# Sheet2_-.net
KiCad netlist of a schematic drawn in Altium Designer
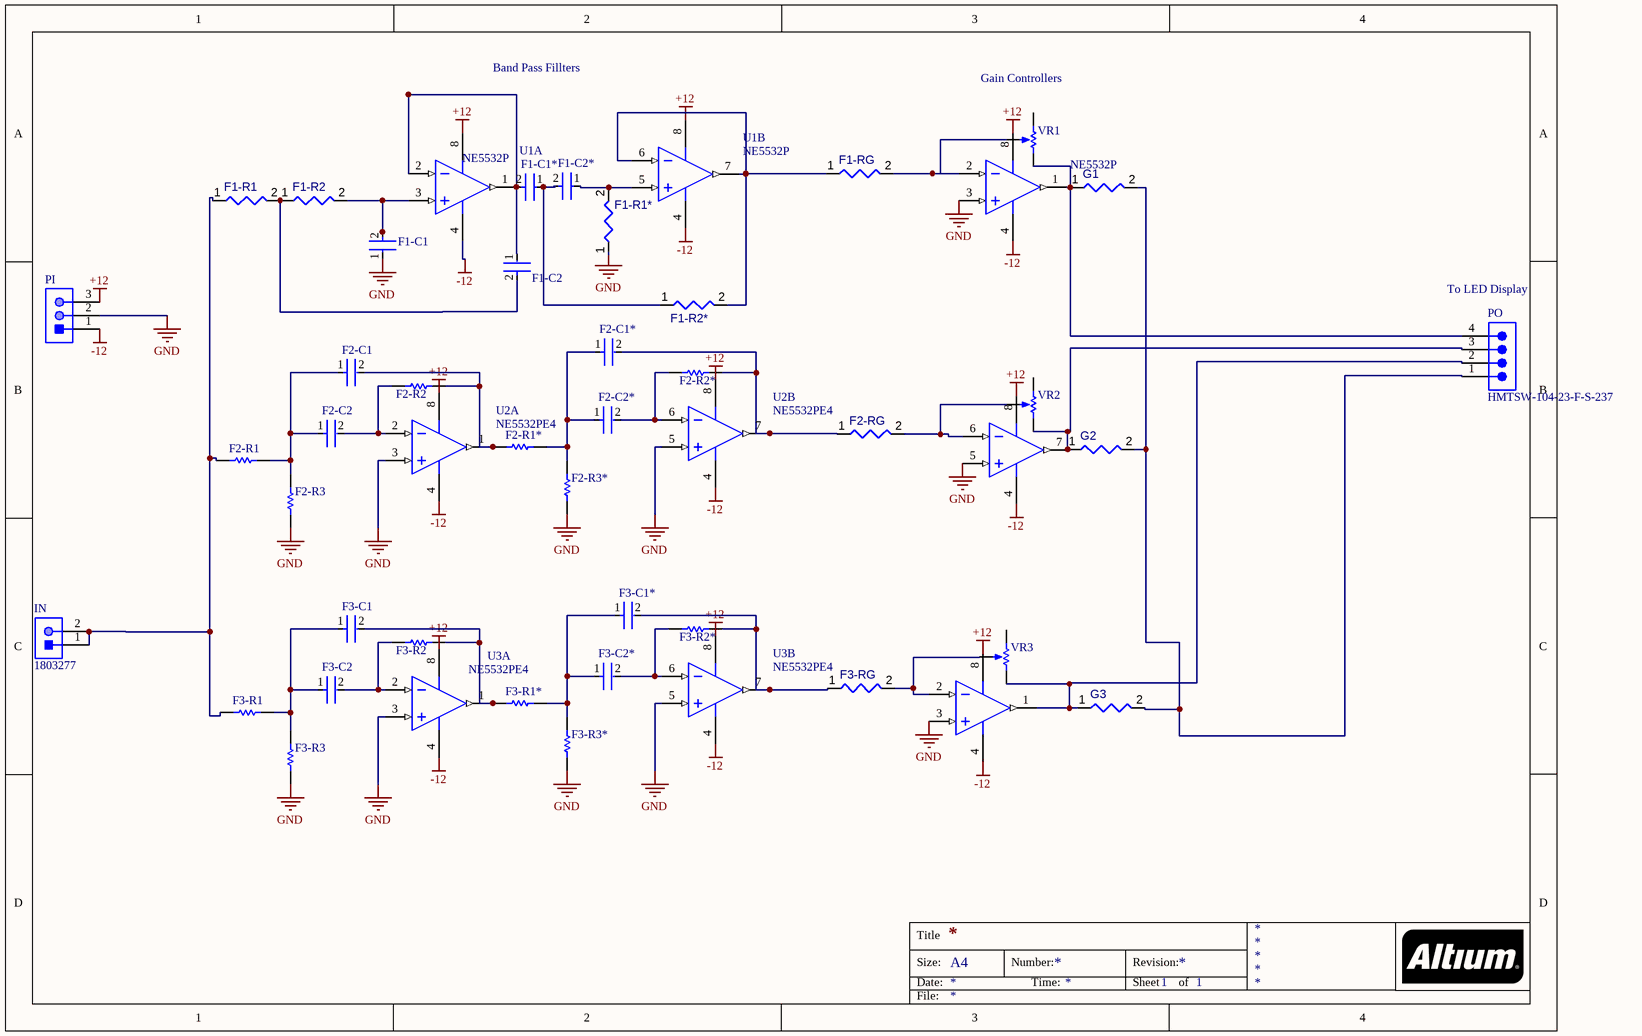
[diagram p0: Sheet2 -.SchDoc]

(export (version "E")
  (design (tool "Eeschema 10.0.6"))
  (components
    (comp (ref "F1-C1")
      (value "VY1102M35Y5UQ6TV0")
      (footprint "FP-VY1102M35Y5UQ6TV0-MFG")
      (description "CAP CER 1000PF 760VAC Y5U RADIAL")
      (fields (field (name "VOLTAGE") "500V") (field (name "TOLERANCE") "20%"))
      (libsource (lib "Altium Content Vault") (part "6d4d395cd7362dd47ce0157d173177e"))
    )
    (comp (ref "F1-C1*")
      (value "VY1102M35Y5UQ6TV0")
      (footprint "FP-VY1102M35Y5UQ6TV0-MFG")
      (description "CAP CER 1000PF 760VAC Y5U RADIAL")
      (fields (field (name "VOLTAGE") "500V") (field (name "TOLERANCE") "20%"))
      (libsource (lib "Altium Content Vault") (part "6d4d395cd7362dd47ce0157d173177e"))
    )
    (comp (ref "F1-C2")
      (value "VY1102M35Y5UQ6TV0")
      (footprint "FP-VY1102M35Y5UQ6TV0-MFG")
      (description "CAP CER 1000PF 760VAC Y5U RADIAL")
      (fields (field (name "VOLTAGE") "500V") (field (name "TOLERANCE") "20%"))
      (libsource (lib "Altium Content Vault") (part "6d4d395cd7362dd47ce0157d173177e"))
    )
    (comp (ref "F1-C2*")
      (value "VY1102M35Y5UQ6TV0")
      (footprint "FP-VY1102M35Y5UQ6TV0-MFG")
      (description "CAP CER 1000PF 760VAC Y5U RADIAL")
      (fields (field (name "VOLTAGE") "500V") (field (name "TOLERANCE") "20%"))
      (libsource (lib "Altium Content Vault") (part "6d4d395cd7362dd47ce0157d173177e"))
    )
    (comp (ref "F1-R1")
      (value "MFR-25FBF52-2K21")
      (footprint "RESA60-630X240")
      (description "Axial Resistor, 2.21 KOhm, +/- 1%, 0.25 W, -55 to 155 degC, 2-Pin THD, RoHS, Bulk")
      (fields (field (name "TOLERANCE") "1%") (field (name "POWER") "250mW"))
      (libsource (lib "Senuda Ratnayake") (part "RES-2"))
    )
    (comp (ref "F1-R1*")
      (value "MFR-25FBF52-2K21")
      (footprint "RESA60-630X240")
      (description "Axial Resistor, 2.21 KOhm, +/- 1%, 0.25 W, -55 to 155 degC, 2-Pin THD, RoHS, Bulk")
      (fields (field (name "TOLERANCE") "1%") (field (name "POWER") "250mW"))
      (libsource (lib "Senuda Ratnayake") (part "RES-2"))
    )
    (comp (ref "F1-R2")
      (value "MFR-25FBF52-2K21")
      (footprint "RESA60-630X240")
      (description "Axial Resistor, 2.21 KOhm, +/- 1%, 0.25 W, -55 to 155 degC, 2-Pin THD, RoHS, Bulk")
      (fields (field (name "TOLERANCE") "1%") (field (name "POWER") "250mW"))
      (libsource (lib "Senuda Ratnayake") (part "RES-2"))
    )
    (comp (ref "F1-R2*")
      (value "MFR-25FBF52-2K21")
      (footprint "RESA60-630X240")
      (description "Axial Resistor, 2.21 KOhm, +/- 1%, 0.25 W, -55 to 155 degC, 2-Pin THD, RoHS, Bulk")
      (fields (field (name "TOLERANCE") "1%") (field (name "POWER") "250mW"))
      (libsource (lib "Senuda Ratnayake") (part "RES-2"))
    )
    (comp (ref "F1-RG")
      (value "MFR-25FBF52-2K21")
      (footprint "RESA60-630X240")
      (description "Axial Resistor, 2.21 KOhm, +/- 1%, 0.25 W, -55 to 155 degC, 2-Pin THD, RoHS, Bulk")
      (fields (field (name "TOLERANCE") "1%") (field (name "POWER") "250mW"))
      (libsource (lib "Senuda Ratnayake") (part "RES-2"))
    )
    (comp (ref "F2-C1")
      (value "VY2102M29Y5US6TV7")
      (footprint "FP-VY2102M29Y5US6TV7-MFG")
      (fields (field (name "VOLTAGE") "300V") (field (name "TOLERANCE") "20%"))
      (libsource (lib "Altium Content Vault") (part "11868f565c42a9108669ba33697ecf6"))
    )
    (comp (ref "F2-C1*")
      (value "VY2102M29Y5US6TV7")
      (footprint "FP-VY2102M29Y5US6TV7-MFG")
      (fields (field (name "VOLTAGE") "300V") (field (name "TOLERANCE") "20%"))
      (libsource (lib "Altium Content Vault") (part "11868f565c42a9108669ba33697ecf6"))
    )
    (comp (ref "F2-C2")
      (value "VY2102M29Y5US6TV7")
      (footprint "FP-VY2102M29Y5US6TV7-MFG")
      (fields (field (name "VOLTAGE") "300V") (field (name "TOLERANCE") "20%"))
      (libsource (lib "Altium Content Vault") (part "11868f565c42a9108669ba33697ecf6"))
    )
    (comp (ref "F2-C2*")
      (value "VY2102M29Y5US6TV7")
      (footprint "FP-VY2102M29Y5US6TV7-MFG")
      (fields (field (name "VOLTAGE") "300V") (field (name "TOLERANCE") "20%"))
      (libsource (lib "Altium Content Vault") (part "11868f565c42a9108669ba33697ecf6"))
    )
    (comp (ref "F2-R1")
      (value "MFR-25FBF52-2K21")
      (footprint "RESA60-630X240")
      (description "Axial Resistor, 2.21 KOhm, +/- 1%, 0.25 W, -55 to 155 degC, 2-Pin THD, RoHS, Bulk")
      (libsource (lib "Altium Content Vault") (part "RES-2"))
    )
    (comp (ref "F2-R1*")
      (value "MFR-25FBF52-2K21")
      (footprint "RESA60-630X240")
      (description "Axial Resistor, 2.21 KOhm, +/- 1%, 0.25 W, -55 to 155 degC, 2-Pin THD, RoHS, Bulk")
      (libsource (lib "Altium Content Vault") (part "RES-2"))
    )
    (comp (ref "F2-R2")
      (value "MFR-25FBF5210K")
      (footprint "RESA60-630X240")
      (description "Axial Resistor, 10 KOhm, +/- 1%, 0.25 W, -55 to 155 degC, 2-Pin THD, RoHS, Bulk")
      (fields (field (name "TOLERANCE") "1%") (field (name "MANUFACTURER") "Yageo"))
      (libsource (lib "Altium Content Vault") (part "RES-2"))
    )
    (comp (ref "F2-R2*")
      (value "MFR-25FBF5210K")
      (footprint "RESA60-630X240")
      (description "Axial Resistor, 10 KOhm, +/- 1%, 0.25 W, -55 to 155 degC, 2-Pin THD, RoHS, Bulk")
      (fields (field (name "TOLERANCE") "1%") (field (name "MANUFACTURER") "Yageo"))
      (libsource (lib "Altium Content Vault") (part "RES-2"))
    )
    (comp (ref "F2-R3")
      (value "MFR-25FBF5210K")
      (footprint "RESA60-630X240")
      (description "Axial Resistor, 10 KOhm, +/- 1%, 0.25 W, -55 to 155 degC, 2-Pin THD, RoHS, Bulk")
      (fields (field (name "TOLERANCE") "1%") (field (name "MANUFACTURER") "Yageo"))
      (libsource (lib "Altium Content Vault") (part "RES-2"))
    )
    (comp (ref "F2-R3*")
      (value "MFR-25FBF5210K")
      (footprint "RESA60-630X240")
      (description "Axial Resistor, 10 KOhm, +/- 1%, 0.25 W, -55 to 155 degC, 2-Pin THD, RoHS, Bulk")
      (fields (field (name "TOLERANCE") "1%") (field (name "MANUFACTURER") "Yageo"))
      (libsource (lib "Altium Content Vault") (part "RES-2"))
    )
    (comp (ref "F2-RG")
      (value "MFR-25FBF52-2K21")
      (footprint "RESA60-630X240")
      (description "Axial Resistor, 2.21 KOhm, +/- 1%, 0.25 W, -55 to 155 degC, 2-Pin THD, RoHS, Bulk")
      (fields (field (name "TOLERANCE") "1%") (field (name "POWER") "250mW"))
      (libsource (lib "Senuda Ratnayake") (part "RES-2"))
    )
    (comp (ref "F3-C1")
      (value "VY2102M29Y5US6TV7")
      (footprint "FP-VY2102M29Y5US6TV7-MFG")
      (fields (field (name "VOLTAGE") "300V") (field (name "TOLERANCE") "20%"))
      (libsource (lib "Altium Content Vault") (part "11868f565c42a9108669ba33697ecf6"))
    )
    (comp (ref "F3-C1*")
      (value "VY2102M29Y5US6TV7")
      (footprint "FP-VY2102M29Y5US6TV7-MFG")
      (fields (field (name "VOLTAGE") "300V") (field (name "TOLERANCE") "20%"))
      (libsource (lib "Altium Content Vault") (part "11868f565c42a9108669ba33697ecf6"))
    )
    (comp (ref "F3-C2")
      (value "VY2102M29Y5US6TV7")
      (footprint "FP-VY2102M29Y5US6TV7-MFG")
      (fields (field (name "VOLTAGE") "300V") (field (name "TOLERANCE") "20%"))
      (libsource (lib "Altium Content Vault") (part "11868f565c42a9108669ba33697ecf6"))
    )
    (comp (ref "F3-C2*")
      (value "VY2102M29Y5US6TV7")
      (footprint "FP-VY2102M29Y5US6TV7-MFG")
      (fields (field (name "VOLTAGE") "300V") (field (name "TOLERANCE") "20%"))
      (libsource (lib "Altium Content Vault") (part "11868f565c42a9108669ba33697ecf6"))
    )
    (comp (ref "F3-R1")
      (value "MFR-25FBF52-2K21")
      (footprint "RESA60-630X240")
      (description "Axial Resistor, 2.21 KOhm, +/- 1%, 0.25 W, -55 to 155 degC, 2-Pin THD, RoHS, Bulk")
      (libsource (lib "Altium Content Vault") (part "RES-2"))
    )
    (comp (ref "F3-R1*")
      (value "MFR-25FBF52-2K21")
      (footprint "RESA60-630X240")
      (description "Axial Resistor, 2.21 KOhm, +/- 1%, 0.25 W, -55 to 155 degC, 2-Pin THD, RoHS, Bulk")
      (libsource (lib "Altium Content Vault") (part "RES-2"))
    )
    (comp (ref "F3-R2")
      (value "MFR-25FBF5210K")
      (footprint "RESA60-630X240")
      (description "Axial Resistor, 10 KOhm, +/- 1%, 0.25 W, -55 to 155 degC, 2-Pin THD, RoHS, Bulk")
      (fields (field (name "TOLERANCE") "1%") (field (name "MANUFACTURER") "Yageo"))
      (libsource (lib "Altium Content Vault") (part "RES-2"))
    )
    (comp (ref "F3-R2*")
      (value "MFR-25FBF5210K")
      (footprint "RESA60-630X240")
      (description "Axial Resistor, 10 KOhm, +/- 1%, 0.25 W, -55 to 155 degC, 2-Pin THD, RoHS, Bulk")
      (fields (field (name "TOLERANCE") "1%") (field (name "MANUFACTURER") "Yageo"))
      (libsource (lib "Altium Content Vault") (part "RES-2"))
    )
    (comp (ref "F3-R3")
      (value "MFR-25FBF5210K")
      (footprint "RESA60-630X240")
      (description "Axial Resistor, 10 KOhm, +/- 1%, 0.25 W, -55 to 155 degC, 2-Pin THD, RoHS, Bulk")
      (fields (field (name "TOLERANCE") "1%") (field (name "MANUFACTURER") "Yageo"))
      (libsource (lib "Altium Content Vault") (part "RES-2"))
    )
    (comp (ref "F3-R3*")
      (value "MFR-25FBF5210K")
      (footprint "RESA60-630X240")
      (description "Axial Resistor, 10 KOhm, +/- 1%, 0.25 W, -55 to 155 degC, 2-Pin THD, RoHS, Bulk")
      (fields (field (name "TOLERANCE") "1%") (field (name "MANUFACTURER") "Yageo"))
      (libsource (lib "Altium Content Vault") (part "RES-2"))
    )
    (comp (ref "F3-RG")
      (value "MFR-25FBF52-2K21")
      (footprint "RESA60-630X240")
      (description "Axial Resistor, 2.21 KOhm, +/- 1%, 0.25 W, -55 to 155 degC, 2-Pin THD, RoHS, Bulk")
      (fields (field (name "TOLERANCE") "1%") (field (name "POWER") "250mW"))
      (libsource (lib "Senuda Ratnayake") (part "RES-2"))
    )
    (comp (ref "G1")
      (value "MFR-25FBF52-2K21")
      (footprint "RESA60-630X240")
      (description "Axial Resistor, 2.21 KOhm, +/- 1%, 0.25 W, -55 to 155 degC, 2-Pin THD, RoHS, Bulk")
      (fields (field (name "TOLERANCE") "1%") (field (name "POWER") "250mW"))
      (libsource (lib "Senuda Ratnayake") (part "RES-2"))
    )
    (comp (ref "G2")
      (value "MFR-25FBF52-2K21")
      (footprint "RESA60-630X240")
      (description "Axial Resistor, 2.21 KOhm, +/- 1%, 0.25 W, -55 to 155 degC, 2-Pin THD, RoHS, Bulk")
      (fields (field (name "TOLERANCE") "1%") (field (name "POWER") "250mW"))
      (libsource (lib "Senuda Ratnayake") (part "RES-2"))
    )
    (comp (ref "G3")
      (value "MFR-25FBF52-2K21")
      (footprint "RESA60-630X240")
      (description "Axial Resistor, 2.21 KOhm, +/- 1%, 0.25 W, -55 to 155 degC, 2-Pin THD, RoHS, Bulk")
      (fields (field (name "TOLERANCE") "1%") (field (name "POWER") "250mW"))
      (libsource (lib "Senuda Ratnayake") (part "RES-2"))
    )
    (comp (ref "IN")
      (value "1803277")
      (footprint "PHOE-1803277_V")
      (description "Male Header, Pitch 3.81 mm, 1 x 2 Position, Height 7.25 mm, Tail Length 3.4 mm, RoHS, Bulk")
      (fields (field (name "MANUFACTURER") "Phoenix Contact"))
      (libsource (lib "Senuda Ratnayake") (part "CN-1P-M-R2"))
    )
    (comp (ref "PI")
      (value "B3P-VH(LF)(SN)")
      (footprint "JST-B3P-VH(LF)(SN)-3_V")
      (fields (field (name "MANUFACTURER") "JST"))
      (libsource (lib "Senuda Ratnayake") (part "CN-1P-M-R3"))
    )
    (comp (ref "PO")
      (value "HMTSW-104-23-F-S-237")
      (footprint "SMTC-HMTSW-104-23-X-S-237")
      (fields (field (name "MANUFACTURER") "Samtec"))
      (libsource (lib "Altium Content Vault") (part "SMTC-HMTSW-104-23-X-S-237"))
    )
    (comp (ref "U1")
      (value "NE5532P")
      (footprint "P0008A")
      (fields (field (name "MANUFACTURER") "Texas Instruments"))
      (libsource (lib "Altium Content Vault") (part "TI-AMP-D6-2-8_D"))
    )
    (comp (ref "U2")
      (value "NE5532PE4")
      (footprint "TI-P8")
      (fields (field (name "MANUFACTURER") "Texas Instruments"))
      (libsource (lib "Altium Content Vault") (part "TI-AMP-D6-2-8_D"))
    )
    (comp (ref "U3")
      (value "NE5532PE4")
      (footprint "TI-P8")
      (fields (field (name "MANUFACTURER") "Texas Instruments"))
      (libsource (lib "Altium Content Vault") (part "TI-AMP-D6-2-8_D"))
    )
    (comp (ref "U4")
      (value "NE5532P")
      (footprint "P0008A")
      (fields (field (name "MANUFACTURER") "Texas Instruments"))
      (libsource (lib "Altium Content Vault") (part "TI-AMP-D6-2-8_D"))
    )
    (comp (ref "U5")
      (value "NE5532P")
      (footprint "P0008A")
      (fields (field (name "MANUFACTURER") "Texas Instruments"))
      (libsource (lib "Altium Content Vault") (part "TI-AMP-D6-2-8_D"))
    )
    (comp (ref "VR1")
      (value "3852A-282-103AL")
      (footprint "BOUR-3852A-282-103AL-3_V")
      (description "Diameter Panel Control, 10 KOhm, +/- 10%, 2 W, -1 to 125 degC, 3-Pin THD, RoHS, Bulk")
      (fields (field (name "TOLERANCE") "±10%") (field (name "MANUFACTURER") "Bourns"))
      (libsource (lib "Altium Content Vault") (part "RES-POT-3"))
    )
    (comp (ref "VR2")
      (value "3852A-282-103AL")
      (footprint "BOUR-3852A-282-103AL-3_V")
      (description "Diameter Panel Control, 10 KOhm, +/- 10%, 2 W, -1 to 125 degC, 3-Pin THD, RoHS, Bulk")
      (fields (field (name "TOLERANCE") "±10%") (field (name "MANUFACTURER") "Bourns"))
      (libsource (lib "Altium Content Vault") (part "RES-POT-3"))
    )
    (comp (ref "VR3")
      (value "3852A-282-103AL")
      (footprint "BOUR-3852A-282-103AL-3_V")
      (description "Diameter Panel Control, 10 KOhm, +/- 10%, 2 W, -1 to 125 degC, 3-Pin THD, RoHS, Bulk")
      (fields (field (name "TOLERANCE") "±10%") (field (name "MANUFACTURER") "Bourns"))
      (libsource (lib "Altium Content Vault") (part "RES-POT-3"))
    )
  )
  (nets
    (net (code "1") (name "+12") (class "Default")
      (node (ref "PI") (pin "3") (pinfunction "3_3") (pintype "passive"))
      (node (ref "U1") (pin "8") (pinfunction "VCC+_8") (pintype "power_in"))
      (node (ref "U2") (pin "8") (pinfunction "VCC+_8") (pintype "power_in"))
      (node (ref "U3") (pin "8") (pinfunction "VCC+_8") (pintype "power_in"))
      (node (ref "U4") (pin "8") (pinfunction "VCC+_8") (pintype "power_in"))
      (node (ref "U5") (pin "8") (pinfunction "VCC+_8") (pintype "power_in"))
    )
    (net (code "2") (name "-12") (class "Default")
      (node (ref "PI") (pin "1") (pinfunction "1_1") (pintype "passive"))
      (node (ref "U1") (pin "4") (pinfunction "VCC-_4") (pintype "power_in"))
      (node (ref "U2") (pin "4") (pinfunction "VCC-_4") (pintype "power_in"))
      (node (ref "U3") (pin "4") (pinfunction "VCC-_4") (pintype "power_in"))
      (node (ref "U4") (pin "4") (pinfunction "VCC-_4") (pintype "power_in"))
      (node (ref "U5") (pin "4") (pinfunction "VCC-_4") (pintype "power_in"))
    )
    (net (code "3") (name "GND") (class "Default")
      (node (ref "F1-C1") (pin "1") (pinfunction "1_1") (pintype "passive"))
      (node (ref "F1-R1*") (pin "1") (pinfunction "1_1") (pintype "passive"))
      (node (ref "F2-R3") (pin "1") (pinfunction "1_1") (pintype "passive"))
      (node (ref "F2-R3*") (pin "1") (pinfunction "1_1") (pintype "passive"))
      (node (ref "F3-R3") (pin "1") (pinfunction "1_1") (pintype "passive"))
      (node (ref "F3-R3*") (pin "1") (pinfunction "1_1") (pintype "passive"))
      (node (ref "PI") (pin "2") (pinfunction "2_2") (pintype "passive"))
      (node (ref "U2") (pin "3") (pinfunction "IN1+_3") (pintype "input"))
      (node (ref "U2") (pin "5") (pinfunction "IN2+_5") (pintype "input"))
      (node (ref "U3") (pin "3") (pinfunction "IN1+_3") (pintype "input"))
      (node (ref "U3") (pin "5") (pinfunction "IN2+_5") (pintype "input"))
      (node (ref "U4") (pin "3") (pinfunction "IN1+_3") (pintype "input"))
      (node (ref "U4") (pin "5") (pinfunction "IN2+_5") (pintype "input"))
      (node (ref "U5") (pin "3") (pinfunction "IN1+_3") (pintype "input"))
    )
    (net (code "4") (name "Net-(F1-C1*-Pad1)") (class "Default")
      (node (ref "F1-C1*") (pin "1") (pinfunction "1_1") (pintype "passive"))
      (node (ref "F1-C2*") (pin "2") (pinfunction "2_2") (pintype "passive"))
      (node (ref "F1-R2*") (pin "1") (pinfunction "1_1") (pintype "passive"))
    )
    (net (code "5") (name "Net-(F1-C2-Pad2)") (class "Default")
      (node (ref "F1-C2") (pin "2") (pinfunction "2_2") (pintype "passive"))
      (node (ref "F1-R1") (pin "2") (pinfunction "2_2") (pintype "passive"))
      (node (ref "F1-R2") (pin "1") (pinfunction "1_1") (pintype "passive"))
    )
    (net (code "6") (name "Net-(F1-R1-Pad1)") (class "Default")
      (node (ref "F1-R1") (pin "1") (pinfunction "1_1") (pintype "passive"))
      (node (ref "F2-R1") (pin "1") (pinfunction "1_1") (pintype "passive"))
      (node (ref "F3-R1") (pin "1") (pinfunction "1_1") (pintype "passive"))
      (node (ref "IN") (pin "1") (pinfunction "1_1") (pintype "passive"))
      (node (ref "IN") (pin "2") (pinfunction "2_2") (pintype "passive"))
    )
    (net (code "7") (name "Net-(F2-C1*-Pad1)") (class "Default")
      (node (ref "F2-C1*") (pin "1") (pinfunction "1_1") (pintype "passive"))
      (node (ref "F2-C2*") (pin "1") (pinfunction "1_1") (pintype "passive"))
      (node (ref "F2-R1*") (pin "2") (pinfunction "2_2") (pintype "passive"))
      (node (ref "F2-R3*") (pin "2") (pinfunction "2_2") (pintype "passive"))
    )
    (net (code "8") (name "Net-(F2-C1-Pad1)") (class "Default")
      (node (ref "F2-C1") (pin "1") (pinfunction "1_1") (pintype "passive"))
      (node (ref "F2-C2") (pin "1") (pinfunction "1_1") (pintype "passive"))
      (node (ref "F2-R1") (pin "2") (pinfunction "2_2") (pintype "passive"))
      (node (ref "F2-R3") (pin "2") (pinfunction "2_2") (pintype "passive"))
    )
    (net (code "9") (name "Net-(F3-C1*-Pad1)") (class "Default")
      (node (ref "F3-C1*") (pin "1") (pinfunction "1_1") (pintype "passive"))
      (node (ref "F3-C2*") (pin "1") (pinfunction "1_1") (pintype "passive"))
      (node (ref "F3-R1*") (pin "2") (pinfunction "2_2") (pintype "passive"))
      (node (ref "F3-R3*") (pin "2") (pinfunction "2_2") (pintype "passive"))
    )
    (net (code "10") (name "Net-(F3-C1-Pad1)") (class "Default")
      (node (ref "F3-C1") (pin "1") (pinfunction "1_1") (pintype "passive"))
      (node (ref "F3-C2") (pin "1") (pinfunction "1_1") (pintype "passive"))
      (node (ref "F3-R1") (pin "2") (pinfunction "2_2") (pintype "passive"))
      (node (ref "F3-R3") (pin "2") (pinfunction "2_2") (pintype "passive"))
    )
    (net (code "11") (name "Net-(G1-Pad2)") (class "Default")
      (node (ref "G1") (pin "2") (pinfunction "2_2") (pintype "passive"))
      (node (ref "G2") (pin "2") (pinfunction "2_2") (pintype "passive"))
      (node (ref "G3") (pin "2") (pinfunction "2_2") (pintype "passive"))
      (node (ref "PO") (pin "1") (pinfunction "1_1") (pintype "passive"))
    )
    (net (code "12") (name "Net-(U1A-IN1+)") (class "Default")
      (node (ref "F1-C1") (pin "2") (pinfunction "2_2") (pintype "passive"))
      (node (ref "F1-R2") (pin "2") (pinfunction "2_2") (pintype "passive"))
      (node (ref "U1") (pin "3") (pinfunction "IN1+_3") (pintype "input"))
    )
    (net (code "13") (name "Net-(U1A-IN1-)") (class "Default")
      (node (ref "F1-C1*") (pin "2") (pinfunction "2_2") (pintype "passive"))
      (node (ref "F1-C2") (pin "1") (pinfunction "1_1") (pintype "passive"))
      (node (ref "U1") (pin "1") (pinfunction "OUT1_1") (pintype "output"))
      (node (ref "U1") (pin "2") (pinfunction "IN1-_2") (pintype "input"))
    )
    (net (code "14") (name "Net-(U1B-IN2+)") (class "Default")
      (node (ref "F1-C2*") (pin "1") (pinfunction "1_1") (pintype "passive"))
      (node (ref "F1-R1*") (pin "2") (pinfunction "2_2") (pintype "passive"))
      (node (ref "U1") (pin "5") (pinfunction "IN2+_5") (pintype "input"))
    )
    (net (code "15") (name "Net-(U1B-IN2-)") (class "Default")
      (node (ref "F1-R2*") (pin "2") (pinfunction "2_2") (pintype "passive"))
      (node (ref "F1-RG") (pin "1") (pinfunction "1_1") (pintype "passive"))
      (node (ref "U1") (pin "6") (pinfunction "IN2-_6") (pintype "input"))
      (node (ref "U1") (pin "7") (pinfunction "OUT2_7") (pintype "output"))
    )
    (net (code "16") (name "Net-(U2A-IN1-)") (class "Default")
      (node (ref "F2-C2") (pin "2") (pinfunction "2_2") (pintype "passive"))
      (node (ref "F2-R2") (pin "2") (pinfunction "2_2") (pintype "passive"))
      (node (ref "U2") (pin "2") (pinfunction "IN1-_2") (pintype "input"))
    )
    (net (code "17") (name "Net-(U2A-OUT1)") (class "Default")
      (node (ref "F2-C1") (pin "2") (pinfunction "2_2") (pintype "passive"))
      (node (ref "F2-R1*") (pin "1") (pinfunction "1_1") (pintype "passive"))
      (node (ref "F2-R2") (pin "1") (pinfunction "1_1") (pintype "passive"))
      (node (ref "U2") (pin "1") (pinfunction "OUT1_1") (pintype "output"))
    )
    (net (code "18") (name "Net-(U2B-IN2-)") (class "Default")
      (node (ref "F2-C2*") (pin "2") (pinfunction "2_2") (pintype "passive"))
      (node (ref "F2-R2*") (pin "2") (pinfunction "2_2") (pintype "passive"))
      (node (ref "U2") (pin "6") (pinfunction "IN2-_6") (pintype "input"))
    )
    (net (code "19") (name "Net-(U2B-OUT2)") (class "Default")
      (node (ref "F2-C1*") (pin "2") (pinfunction "2_2") (pintype "passive"))
      (node (ref "F2-R2*") (pin "1") (pinfunction "1_1") (pintype "passive"))
      (node (ref "F2-RG") (pin "1") (pinfunction "1_1") (pintype "passive"))
      (node (ref "U2") (pin "7") (pinfunction "OUT2_7") (pintype "output"))
    )
    (net (code "20") (name "Net-(U3A-IN1-)") (class "Default")
      (node (ref "F3-C2") (pin "2") (pinfunction "2_2") (pintype "passive"))
      (node (ref "F3-R2") (pin "2") (pinfunction "2_2") (pintype "passive"))
      (node (ref "U3") (pin "2") (pinfunction "IN1-_2") (pintype "input"))
    )
    (net (code "21") (name "Net-(U3A-OUT1)") (class "Default")
      (node (ref "F3-C1") (pin "2") (pinfunction "2_2") (pintype "passive"))
      (node (ref "F3-R1*") (pin "1") (pinfunction "1_1") (pintype "passive"))
      (node (ref "F3-R2") (pin "1") (pinfunction "1_1") (pintype "passive"))
      (node (ref "U3") (pin "1") (pinfunction "OUT1_1") (pintype "output"))
    )
    (net (code "22") (name "Net-(U3B-IN2-)") (class "Default")
      (node (ref "F3-C2*") (pin "2") (pinfunction "2_2") (pintype "passive"))
      (node (ref "F3-R2*") (pin "2") (pinfunction "2_2") (pintype "passive"))
      (node (ref "U3") (pin "6") (pinfunction "IN2-_6") (pintype "input"))
    )
    (net (code "23") (name "Net-(U3B-OUT2)") (class "Default")
      (node (ref "F3-C1*") (pin "2") (pinfunction "2_2") (pintype "passive"))
      (node (ref "F3-R2*") (pin "1") (pinfunction "1_1") (pintype "passive"))
      (node (ref "F3-RG") (pin "1") (pinfunction "1_1") (pintype "passive"))
      (node (ref "U3") (pin "7") (pinfunction "OUT2_7") (pintype "output"))
    )
    (net (code "24") (name "Net-(U4A-IN1-)") (class "Default")
      (node (ref "F1-RG") (pin "2") (pinfunction "2_2") (pintype "passive"))
      (node (ref "U4") (pin "2") (pinfunction "IN1-_2") (pintype "input"))
      (node (ref "VR1") (pin "2") (pinfunction "S_2") (pintype "passive"))
    )
    (net (code "25") (name "Net-(U4A-OUT1)") (class "Default")
      (node (ref "G1") (pin "1") (pinfunction "1_1") (pintype "passive"))
      (node (ref "PO") (pin "4") (pinfunction "4_4") (pintype "passive"))
      (node (ref "U4") (pin "1") (pinfunction "OUT1_1") (pintype "output"))
      (node (ref "VR1") (pin "3") (pinfunction "CW_3") (pintype "passive"))
    )
    (net (code "26") (name "Net-(U4B-IN2-)") (class "Default")
      (node (ref "F2-RG") (pin "2") (pinfunction "2_2") (pintype "passive"))
      (node (ref "U4") (pin "6") (pinfunction "IN2-_6") (pintype "input"))
      (node (ref "VR2") (pin "2") (pinfunction "S_2") (pintype "passive"))
    )
    (net (code "27") (name "Net-(U4B-OUT2)") (class "Default")
      (node (ref "G2") (pin "1") (pinfunction "1_1") (pintype "passive"))
      (node (ref "PO") (pin "3") (pinfunction "3_3") (pintype "passive"))
      (node (ref "U4") (pin "7") (pinfunction "OUT2_7") (pintype "output"))
      (node (ref "VR2") (pin "3") (pinfunction "CW_3") (pintype "passive"))
    )
    (net (code "28") (name "Net-(U5A-IN1-)") (class "Default")
      (node (ref "F3-RG") (pin "2") (pinfunction "2_2") (pintype "passive"))
      (node (ref "U5") (pin "2") (pinfunction "IN1-_2") (pintype "input"))
      (node (ref "VR3") (pin "2") (pinfunction "S_2") (pintype "passive"))
    )
    (net (code "29") (name "Net-(U5A-OUT1)") (class "Default")
      (node (ref "G3") (pin "1") (pinfunction "1_1") (pintype "passive"))
      (node (ref "PO") (pin "2") (pinfunction "2_2") (pintype "passive"))
      (node (ref "U5") (pin "1") (pinfunction "OUT1_1") (pintype "output"))
      (node (ref "VR3") (pin "3") (pinfunction "CW_3") (pintype "passive"))
    )
    (net (code "30") (name "unconnected-(VR1-CCW-Pad1)") (class "Default")
      (node (ref "VR1") (pin "1") (pinfunction "CCW_1") (pintype "passive"))
    )
    (net (code "31") (name "unconnected-(VR2-CCW-Pad1)") (class "Default")
      (node (ref "VR2") (pin "1") (pinfunction "CCW_1") (pintype "passive"))
    )
    (net (code "32") (name "unconnected-(VR3-CCW-Pad1)") (class "Default")
      (node (ref "VR3") (pin "1") (pinfunction "CCW_1") (pintype "passive"))
    )
  )
)
